# inverting_amplifier.net
KiCad netlist of a schematic drawn in EAGLE
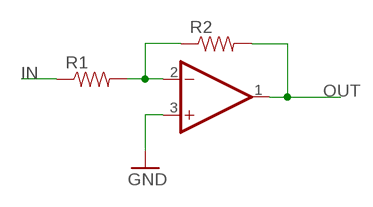
[diagram p0: schematic, sheet 1]

(export (version "E")
  (design (tool "Eeschema 10.0.6"))
  (components
    (comp (ref "IC1")
      (value "MCP6022")
      (footprint "eagle-import:SOIC8_150MIL")
      (libsource (lib "eagle-import") (part "MCP6022"))
    )
    (comp (ref "R1")
      (value "RESISTOR0402-RES")
      (footprint "eagle-import:0402-RES")
      (libsource (lib "eagle-import") (part "RESISTOR0402-RES"))
    )
    (comp (ref "R2")
      (value "RESISTOR0402-RES")
      (footprint "eagle-import:0402-RES")
      (libsource (lib "eagle-import") (part "RESISTOR0402-RES"))
    )
  )
  (nets
    (net (code "1") (name "/IN") (class "Default")
      (node (ref "R1") (pin "1") (pinfunction "1_1") (pintype "passive"))
    )
    (net (code "2") (name "/OUT") (class "Default")
      (node (ref "IC1") (pin "1") (pinfunction "OUT_1") (pintype "output"))
      (node (ref "R2") (pin "2") (pinfunction "2_2") (pintype "passive"))
    )
    (net (code "3") (name "GND") (class "Default")
      (node (ref "IC1") (pin "3") (pinfunction "+IN_3") (pintype "input"))
    )
    (net (code "4") (name "Net-(IC1A--IN)") (class "Default")
      (node (ref "IC1") (pin "2") (pinfunction "-IN_2") (pintype "input"))
      (node (ref "R1") (pin "2") (pinfunction "2_2") (pintype "passive"))
      (node (ref "R2") (pin "1") (pinfunction "1_1") (pintype "passive"))
    )
  )
)
